# BHOnOfreBoard.net
KiCad netlist of a schematic drawn in EAGLE
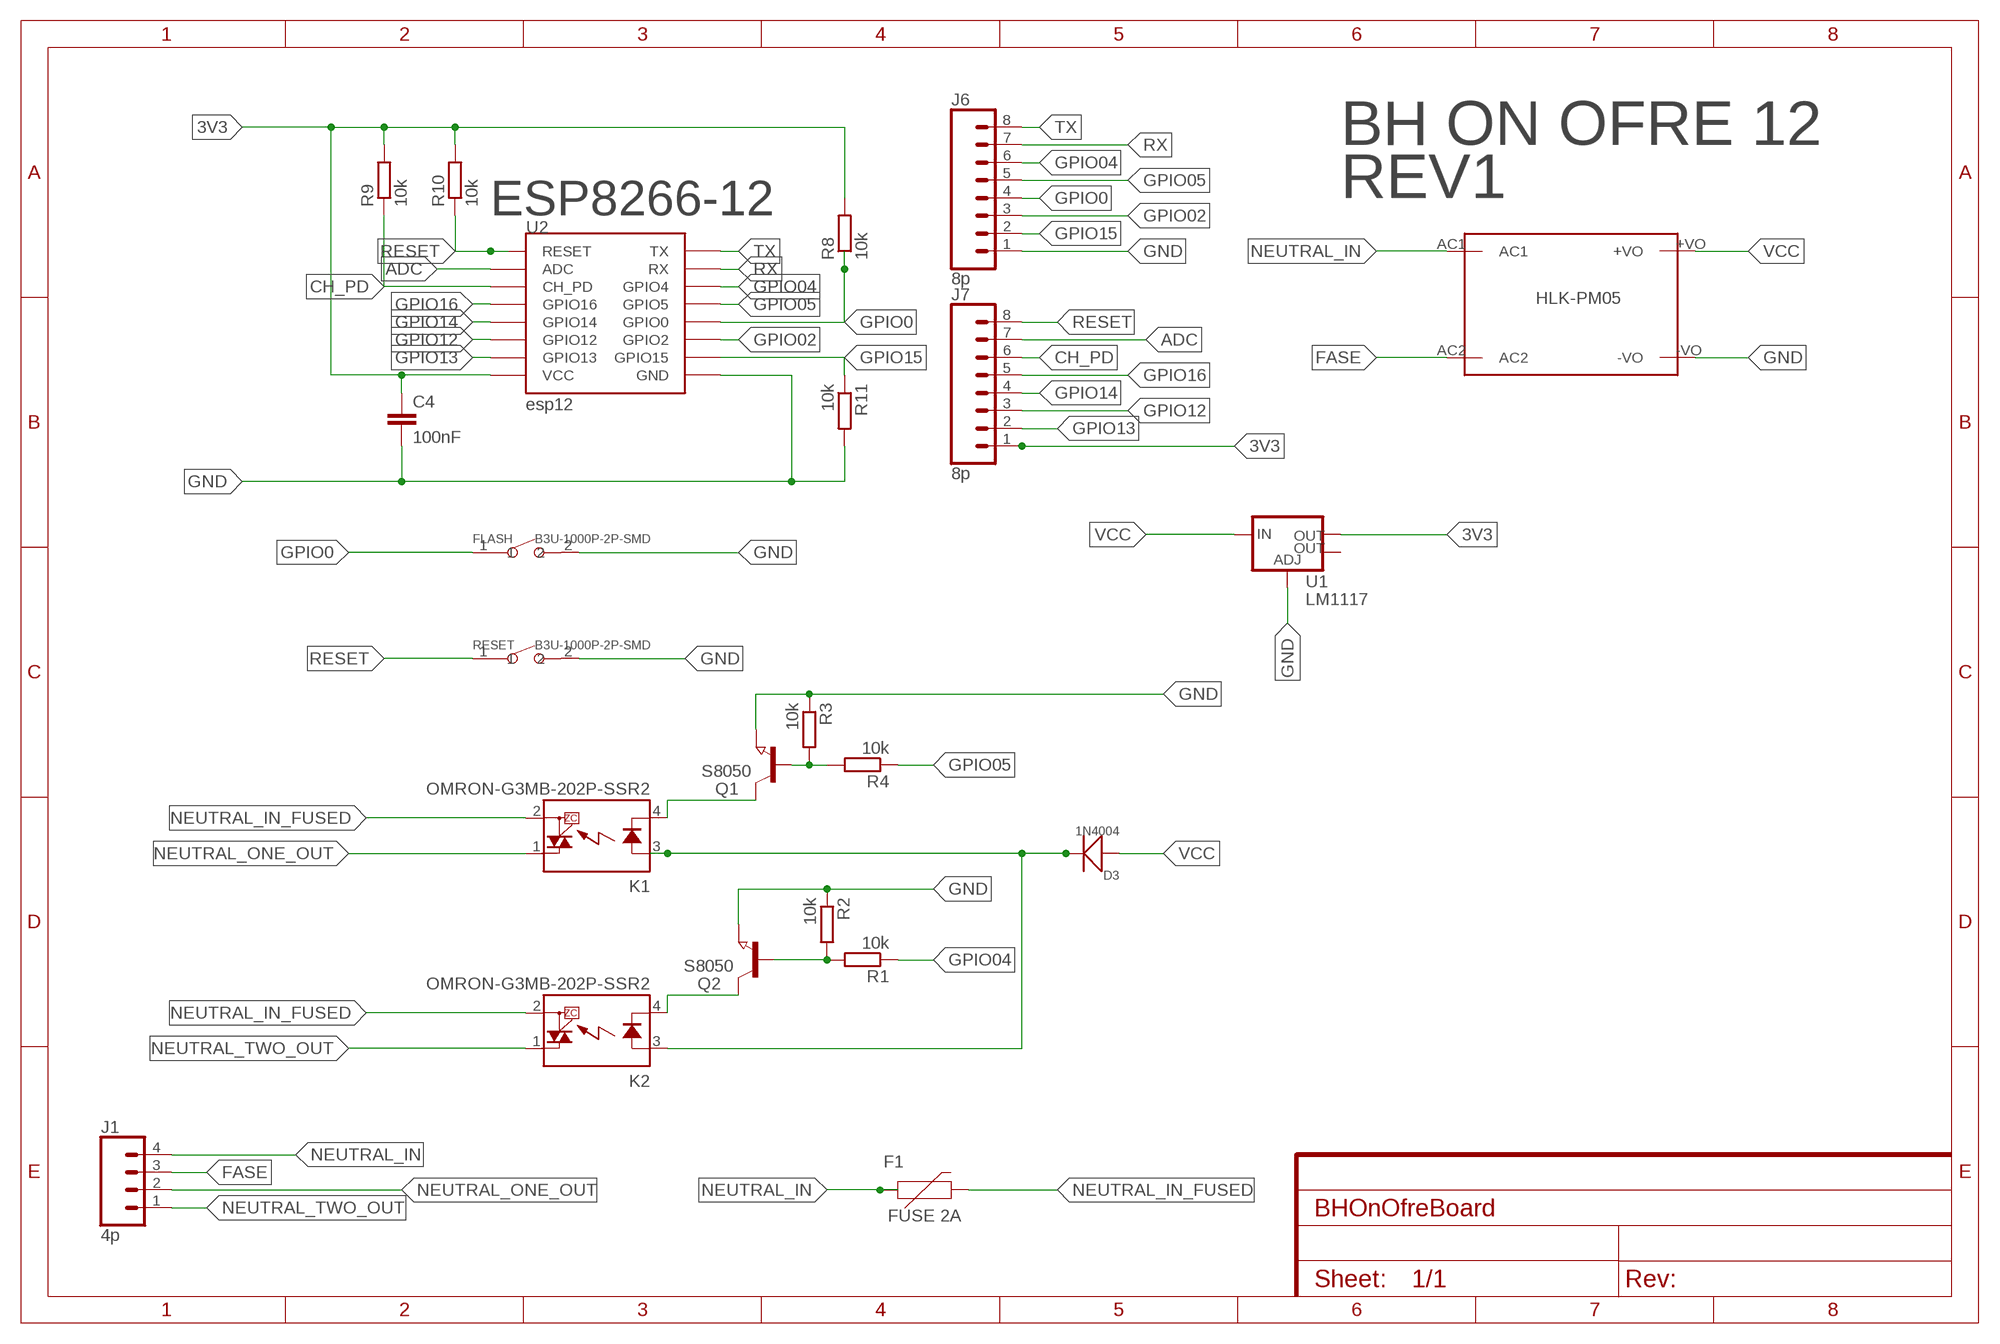
[diagram p0: schematic, sheet 1]

(export (version "E")
  (design (tool "Eeschema 10.0.6"))
  (components
    (comp (ref "C4")
      (value "100nF")
      (footprint "eagle-import:0603")
      (libsource (lib "eagle-import") (part "10NF-0603-50V-10%"))
    )
    (comp (ref "D3")
      (value "1N4004")
      (footprint "eagle-import:DO-214AC")
      (fields (field (name "MPN") "1N4007"))
      (libsource (lib "eagle-import") (part "DIODE-GEN-PURPOSE-1KV-1A(DO-214AC)"))
    )
    (comp (ref "F1")
      (value "FUSE 2A")
      (footprint "eagle-import:PTH")
      (libsource (lib "eagle-import") (part "PPTC_PTH"))
    )
    (comp (ref "FLASH")
      (value "B3U-1000P-2P-SMD")
      (footprint "eagle-import:SW2-2.6-3.0X2.5X1.2+0.4MM")
      (libsource (lib "eagle-import") (part "SMD-BUTTON(2P-3.0X2.5X1.2+0.4MM)-B3U-1000P-2P-SMD"))
    )
    (comp (ref "J1")
      (value "4p")
      (footprint "eagle-import:SCREWTERMINAL-3.5MM-4")
      (libsource (lib "eagle-import") (part "CONN_04SCREW"))
    )
    (comp (ref "J6")
      (value "8p")
      (footprint "eagle-import:1X08")
      (libsource (lib "eagle-import") (part "CONN_08{dblquote}"))
    )
    (comp (ref "J7")
      (value "8p")
      (footprint "eagle-import:1X08")
      (libsource (lib "eagle-import") (part "CONN_08{dblquote}"))
    )
    (comp (ref "K1")
      (value "OMRON-G3MB-202P-SSR2")
      (footprint "eagle-import:OMRON-G3MB-202P-SSR")
      (fields (field (name "MPN") "S202S02F"))
      (libsource (lib "eagle-import") (part "OMRON-G3MB-202P-SSR2"))
    )
    (comp (ref "K2")
      (value "OMRON-G3MB-202P-SSR2")
      (footprint "eagle-import:OMRON-G3MB-202P-SSR")
      (fields (field (name "MPN") "S202S02F"))
      (libsource (lib "eagle-import") (part "OMRON-G3MB-202P-SSR2"))
    )
    (comp (ref "Q1")
      (value "S8050")
      (footprint "eagle-import:SOT23")
      (libsource (lib "eagle-import") (part "NPN-TRANSISTOR_SOT23"))
    )
    (comp (ref "Q2")
      (value "S8050")
      (footprint "eagle-import:SOT23")
      (libsource (lib "eagle-import") (part "NPN-TRANSISTOR_SOT23"))
    )
    (comp (ref "R1")
      (value "10k")
      (footprint "eagle-import:R0603")
      (libsource (lib "eagle-import") (part "R-EU_R0603"))
    )
    (comp (ref "R2")
      (value "10k")
      (footprint "eagle-import:R0603")
      (libsource (lib "eagle-import") (part "R-EU_R0603"))
    )
    (comp (ref "R3")
      (value "10k")
      (footprint "eagle-import:R0603")
      (libsource (lib "eagle-import") (part "R-EU_R0603"))
    )
    (comp (ref "R4")
      (value "10k")
      (footprint "eagle-import:R0603")
      (libsource (lib "eagle-import") (part "R-EU_R0603"))
    )
    (comp (ref "R8")
      (value "10k")
      (footprint "eagle-import:R0603")
      (libsource (lib "eagle-import") (part "R-EU_R0603"))
    )
    (comp (ref "R9")
      (value "10k")
      (footprint "eagle-import:R0603")
      (libsource (lib "eagle-import") (part "R-EU_R0603"))
    )
    (comp (ref "R10")
      (value "10k")
      (footprint "eagle-import:R0603")
      (libsource (lib "eagle-import") (part "R-EU_R0603"))
    )
    (comp (ref "R11")
      (value "10k")
      (footprint "eagle-import:R0603")
      (libsource (lib "eagle-import") (part "R-EU_R0603"))
    )
    (comp (ref "RESET")
      (value "B3U-1000P-2P-SMD")
      (footprint "eagle-import:SW2-2.6-3.0X2.5X1.2+0.4MM")
      (libsource (lib "eagle-import") (part "SMD-BUTTON(2P-3.0X2.5X1.2+0.4MM)-B3U-1000P-2P-SMD"))
    )
    (comp (ref "U$2")
      (value "HLK-PM03")
      (footprint "eagle-import:HLK-PM03")
      (libsource (lib "eagle-import") (part "HLK-PM03"))
    )
    (comp (ref "U1")
      (value "LM1117")
      (footprint "eagle-import:SOT223")
      (libsource (lib "eagle-import") (part "V_REG_LM1117SOT223"))
    )
    (comp (ref "U2")
      (value "esp12")
      (footprint "eagle-import:ESP12-SMD")
      (libsource (lib "eagle-import") (part "ESP12SMD"))
    )
  )
  (nets
    (net (code "1") (name "3V3") (class "Default")
      (node (ref "C4") (pin "1") (pinfunction "1_1") (pintype "passive"))
      (node (ref "J7") (pin "1") (pinfunction "1_1") (pintype "passive"))
      (node (ref "R10") (pin "2") (pinfunction "2_2") (pintype "passive"))
      (node (ref "R8") (pin "2") (pinfunction "2_2") (pintype "passive"))
      (node (ref "R9") (pin "2") (pinfunction "2_2") (pintype "passive"))
      (node (ref "U1") (pin "2") (pinfunction "OUT_2") (pintype "output"))
      (node (ref "U2") (pin "VCC") (pinfunction "VCC_VCC") (pintype "bidirectional"))
    )
    (net (code "2") (name "ADC") (class "Default")
      (node (ref "J7") (pin "7") (pinfunction "7_7") (pintype "passive"))
      (node (ref "U2") (pin "ADC") (pinfunction "ADC_ADC") (pintype "bidirectional"))
    )
    (net (code "3") (name "CH_PD") (class "Default")
      (node (ref "J7") (pin "6") (pinfunction "6_6") (pintype "passive"))
      (node (ref "R9") (pin "1") (pinfunction "1_1") (pintype "passive"))
      (node (ref "U2") (pin "CH_PD") (pinfunction "CH_PD_CH_PD") (pintype "bidirectional"))
    )
    (net (code "4") (name "FASE") (class "Default")
      (node (ref "J1") (pin "3") (pinfunction "3_3") (pintype "passive"))
      (node (ref "U$2") (pin "AC2") (pinfunction "AC2_AC2") (pintype "bidirectional"))
    )
    (net (code "5") (name "GND") (class "Default")
      (node (ref "C4") (pin "2") (pinfunction "2_2") (pintype "passive"))
      (node (ref "FLASH") (pin "2") (pinfunction "2_2") (pintype "bidirectional"))
      (node (ref "J6") (pin "1") (pinfunction "1_1") (pintype "passive"))
      (node (ref "Q1") (pin "2") (pinfunction "E_2") (pintype "passive"))
      (node (ref "Q2") (pin "2") (pinfunction "E_2") (pintype "passive"))
      (node (ref "R11") (pin "2") (pinfunction "2_2") (pintype "passive"))
      (node (ref "R2") (pin "1") (pinfunction "1_1") (pintype "passive"))
      (node (ref "R3") (pin "1") (pinfunction "1_1") (pintype "passive"))
      (node (ref "RESET") (pin "2") (pinfunction "2_2") (pintype "bidirectional"))
      (node (ref "U$2") (pin "-VO") (pinfunction "-VO_-VO") (pintype "bidirectional"))
      (node (ref "U1") (pin "1") (pinfunction "ADJ_1") (pintype "input"))
      (node (ref "U2") (pin "GND") (pinfunction "GND_GND") (pintype "bidirectional"))
    )
    (net (code "6") (name "GPIO0") (class "Default")
      (node (ref "FLASH") (pin "1") (pinfunction "1_1") (pintype "bidirectional"))
      (node (ref "J6") (pin "4") (pinfunction "4_4") (pintype "passive"))
      (node (ref "R8") (pin "1") (pinfunction "1_1") (pintype "passive"))
      (node (ref "U2") (pin "GPIO0") (pinfunction "GPIO0_GPIO0") (pintype "bidirectional"))
    )
    (net (code "7") (name "GPIO02") (class "Default")
      (node (ref "J6") (pin "3") (pinfunction "3_3") (pintype "passive"))
      (node (ref "U2") (pin "GPIO2") (pinfunction "GPIO2_GPIO2") (pintype "bidirectional"))
    )
    (net (code "8") (name "GPIO04") (class "Default")
      (node (ref "J6") (pin "6") (pinfunction "6_6") (pintype "passive"))
      (node (ref "R1") (pin "1") (pinfunction "1_1") (pintype "passive"))
      (node (ref "U2") (pin "GPIO4") (pinfunction "GPIO4_GPIO4") (pintype "bidirectional"))
    )
    (net (code "9") (name "GPIO05") (class "Default")
      (node (ref "J6") (pin "5") (pinfunction "5_5") (pintype "passive"))
      (node (ref "R4") (pin "1") (pinfunction "1_1") (pintype "passive"))
      (node (ref "U2") (pin "GPIO5") (pinfunction "GPIO5_GPIO5") (pintype "bidirectional"))
    )
    (net (code "10") (name "GPIO12") (class "Default")
      (node (ref "J7") (pin "3") (pinfunction "3_3") (pintype "passive"))
      (node (ref "U2") (pin "GPIO12") (pinfunction "GPIO12_GPIO12") (pintype "bidirectional"))
    )
    (net (code "11") (name "GPIO13") (class "Default")
      (node (ref "J7") (pin "2") (pinfunction "2_2") (pintype "passive"))
      (node (ref "U2") (pin "GPIO13") (pinfunction "GPIO13_GPIO13") (pintype "bidirectional"))
    )
    (net (code "12") (name "GPIO14") (class "Default")
      (node (ref "J7") (pin "4") (pinfunction "4_4") (pintype "passive"))
      (node (ref "U2") (pin "GPIO14") (pinfunction "GPIO14_GPIO14") (pintype "bidirectional"))
    )
    (net (code "13") (name "GPIO15") (class "Default")
      (node (ref "J6") (pin "2") (pinfunction "2_2") (pintype "passive"))
      (node (ref "R11") (pin "1") (pinfunction "1_1") (pintype "passive"))
      (node (ref "U2") (pin "GPIO15") (pinfunction "GPIO15_GPIO15") (pintype "bidirectional"))
    )
    (net (code "14") (name "GPIO16") (class "Default")
      (node (ref "J7") (pin "5") (pinfunction "5_5") (pintype "passive"))
      (node (ref "U2") (pin "GPIO16") (pinfunction "GPIO16_GPIO16") (pintype "bidirectional"))
    )
    (net (code "15") (name "NEUTRAL_IN") (class "Default")
      (node (ref "F1") (pin "P$1") (pinfunction "1_P$1") (pintype "bidirectional"))
      (node (ref "J1") (pin "4") (pinfunction "4_4") (pintype "passive"))
      (node (ref "U$2") (pin "AC1") (pinfunction "AC1_AC1") (pintype "bidirectional"))
    )
    (net (code "16") (name "NEUTRAL_IN_FUSED") (class "Default")
      (node (ref "F1") (pin "P$2") (pinfunction "2_P$2") (pintype "bidirectional"))
      (node (ref "K1") (pin "2") (pinfunction "DS2_2") (pintype "passive"))
      (node (ref "K2") (pin "2") (pinfunction "DS2_2") (pintype "passive"))
    )
    (net (code "17") (name "NEUTRAL_ONE_OUT") (class "Default")
      (node (ref "J1") (pin "2") (pinfunction "2_2") (pintype "passive"))
      (node (ref "K1") (pin "1") (pinfunction "DS1_1") (pintype "passive"))
    )
    (net (code "18") (name "NEUTRAL_TWO_OUT") (class "Default")
      (node (ref "J1") (pin "1") (pinfunction "1_1") (pintype "passive"))
      (node (ref "K2") (pin "1") (pinfunction "DS1_1") (pintype "passive"))
    )
    (net (code "19") (name "Net-(D3--)") (class "Default")
      (node (ref "D3") (pin "2") (pinfunction "-_2") (pintype "passive"))
      (node (ref "K1") (pin "3") (pinfunction "A_3") (pintype "passive"))
      (node (ref "K2") (pin "3") (pinfunction "A_3") (pintype "passive"))
    )
    (net (code "20") (name "Net-(K1-K)") (class "Default")
      (node (ref "K1") (pin "4") (pinfunction "K_4") (pintype "passive"))
      (node (ref "Q1") (pin "3") (pinfunction "C_3") (pintype "passive"))
    )
    (net (code "21") (name "Net-(K2-K)") (class "Default")
      (node (ref "K2") (pin "4") (pinfunction "K_4") (pintype "passive"))
      (node (ref "Q2") (pin "3") (pinfunction "C_3") (pintype "passive"))
    )
    (net (code "22") (name "Net-(Q1-B)") (class "Default")
      (node (ref "Q1") (pin "1") (pinfunction "B_1") (pintype "passive"))
      (node (ref "R3") (pin "2") (pinfunction "2_2") (pintype "passive"))
      (node (ref "R4") (pin "2") (pinfunction "2_2") (pintype "passive"))
    )
    (net (code "23") (name "Net-(Q2-B)") (class "Default")
      (node (ref "Q2") (pin "1") (pinfunction "B_1") (pintype "passive"))
      (node (ref "R1") (pin "2") (pinfunction "2_2") (pintype "passive"))
      (node (ref "R2") (pin "2") (pinfunction "2_2") (pintype "passive"))
    )
    (net (code "24") (name "RESET") (class "Default")
      (node (ref "J7") (pin "8") (pinfunction "8_8") (pintype "passive"))
      (node (ref "R10") (pin "1") (pinfunction "1_1") (pintype "passive"))
      (node (ref "RESET") (pin "1") (pinfunction "1_1") (pintype "bidirectional"))
      (node (ref "U2") (pin "RESET") (pinfunction "RESET_RESET") (pintype "bidirectional"))
    )
    (net (code "25") (name "RX") (class "Default")
      (node (ref "J6") (pin "7") (pinfunction "7_7") (pintype "passive"))
      (node (ref "U2") (pin "RXD0") (pinfunction "RX_RXD0") (pintype "bidirectional"))
    )
    (net (code "26") (name "TX") (class "Default")
      (node (ref "J6") (pin "8") (pinfunction "8_8") (pintype "passive"))
      (node (ref "U2") (pin "TXD0") (pinfunction "TX_TXD0") (pintype "bidirectional"))
    )
    (net (code "27") (name "VCC") (class "Default")
      (node (ref "D3") (pin "1") (pinfunction "+_1") (pintype "passive"))
      (node (ref "U$2") (pin "+VO") (pinfunction "+VO_+VO") (pintype "bidirectional"))
      (node (ref "U1") (pin "3") (pinfunction "IN_3") (pintype "input"))
    )
    (net (code "28") (name "unconnected-(U1-OUT-Pad4)") (class "Default")
      (node (ref "U1") (pin "4") (pinfunction "OUT_4") (pintype "output"))
    )
  )
)
